# NES_Controller_Board.net
KiCad netlist of a schematic drawn in EAGLE
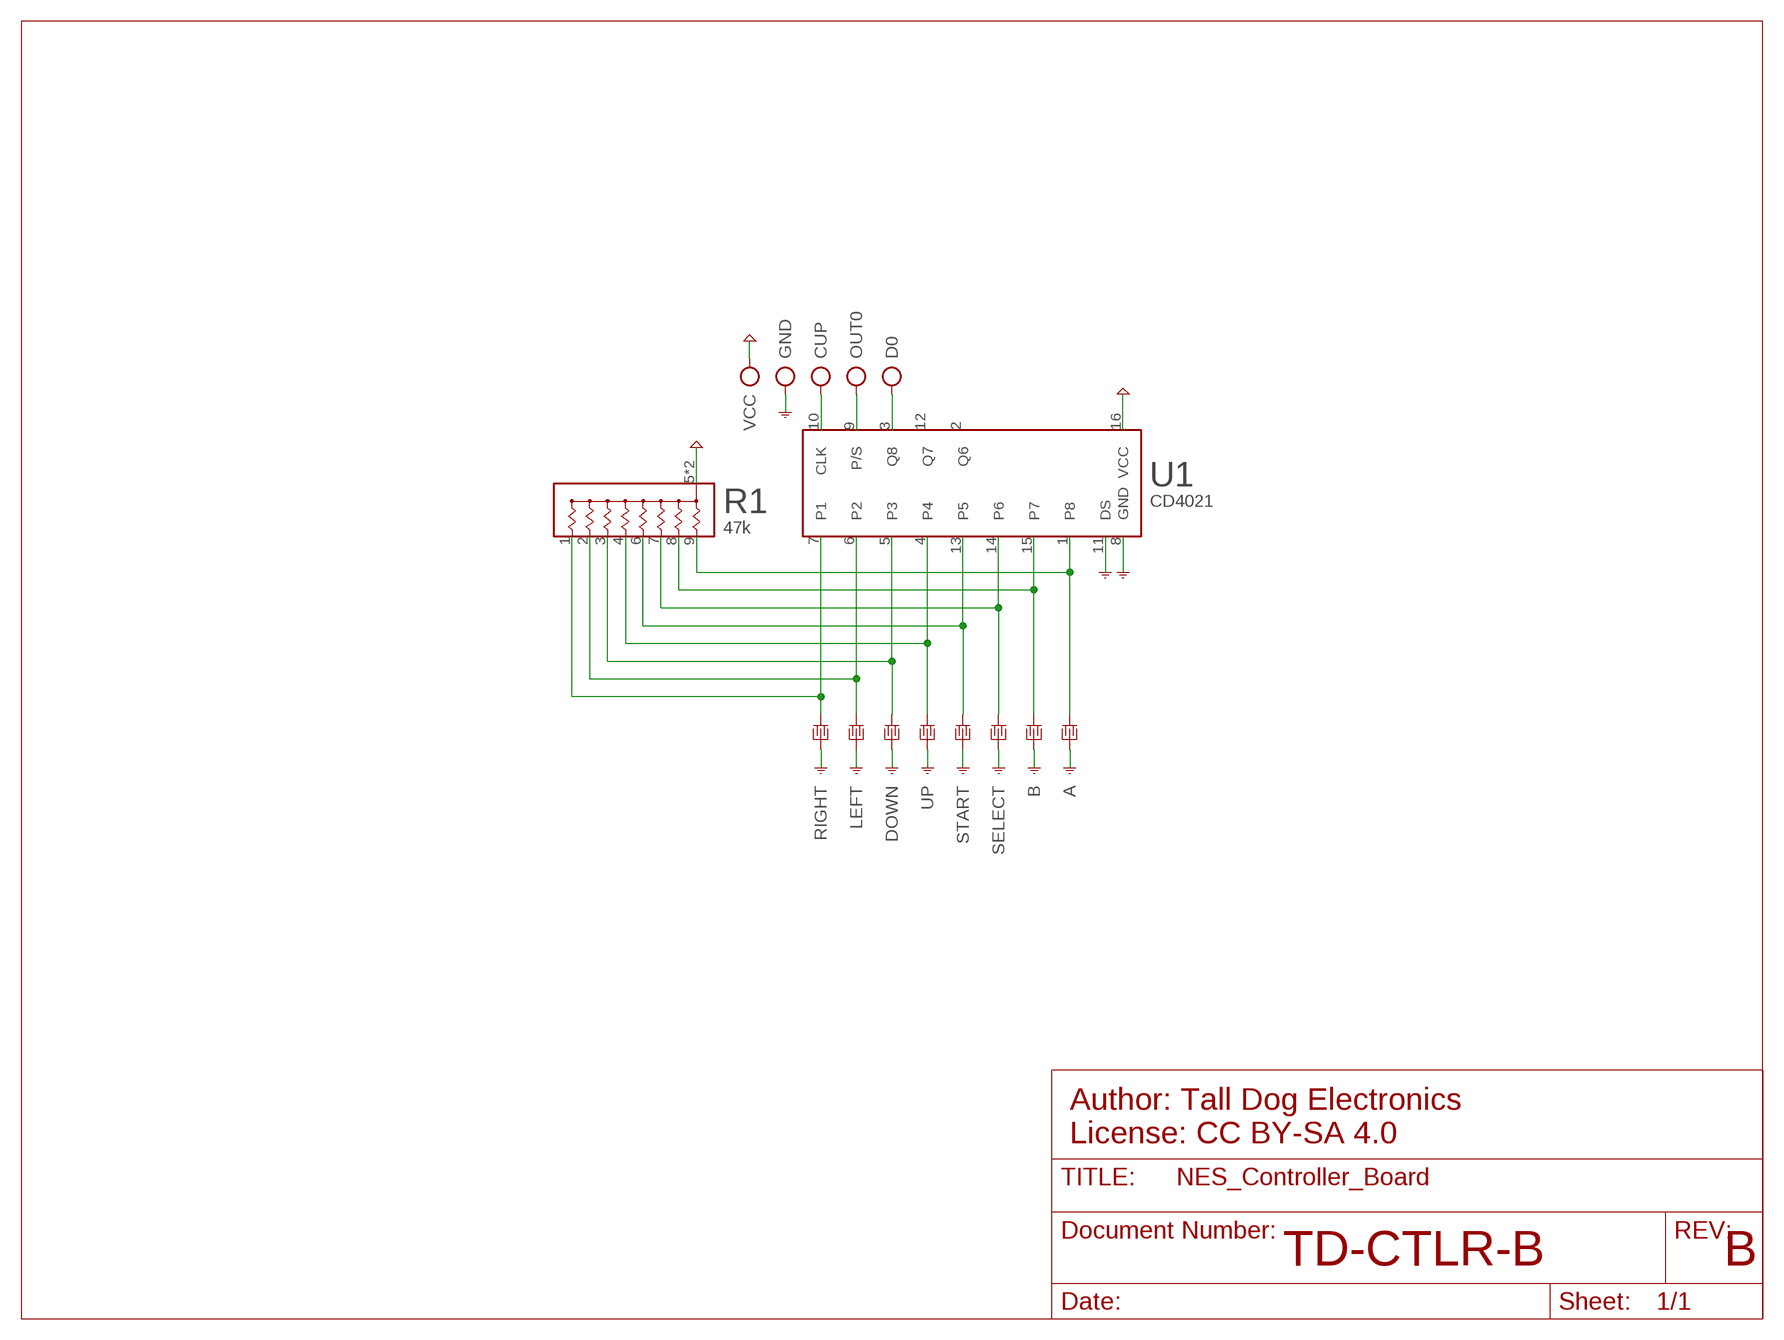
[diagram p0: schematic, sheet 1]

(export (version "E")
  (design (tool "Eeschema 10.0.6"))
  (components
    (comp (ref "A")
      (value "BUTTON-PAD-AB")
      (footprint "eagle-import:CTRL-AB")
      (libsource (lib "eagle-import") (part "BUTTON-PAD-AB"))
    )
    (comp (ref "B")
      (value "BUTTON-PAD-AB")
      (footprint "eagle-import:CTRL-AB")
      (libsource (lib "eagle-import") (part "BUTTON-PAD-AB"))
    )
    (comp (ref "CUP")
      (value "2/RD")
      (footprint "eagle-import:PTH-STRAIN")
      (libsource (lib "eagle-import") (part "HOLE"))
    )
    (comp (ref "D0")
      (value "4/YL")
      (footprint "eagle-import:PTH-STRAIN")
      (libsource (lib "eagle-import") (part "HOLE"))
    )
    (comp (ref "DOWN")
      (value "BUTTON-PAD-DPAD")
      (footprint "eagle-import:CTRL-DPAD")
      (libsource (lib "eagle-import") (part "BUTTON-PAD-DPAD"))
    )
    (comp (ref "GND")
      (value "1/BN")
      (footprint "eagle-import:PTH-STRAIN")
      (libsource (lib "eagle-import") (part "HOLE"))
    )
    (comp (ref "LEFT")
      (value "BUTTON-PAD-DPAD")
      (footprint "eagle-import:CTRL-DPAD")
      (libsource (lib "eagle-import") (part "BUTTON-PAD-DPAD"))
    )
    (comp (ref "OUT0")
      (value "3/OR")
      (footprint "eagle-import:PTH-STRAIN")
      (libsource (lib "eagle-import") (part "HOLE"))
    )
    (comp (ref "R1")
      (value "47k")
      (footprint "eagle-import:EXBA10P")
      (libsource (lib "eagle-import") (part "RA8"))
    )
    (comp (ref "RIGHT")
      (value "BUTTON-PAD-DPAD")
      (footprint "eagle-import:CTRL-DPAD")
      (libsource (lib "eagle-import") (part "BUTTON-PAD-DPAD"))
    )
    (comp (ref "SELECT")
      (value "BUTTON-PAD-STSEL")
      (footprint "eagle-import:CTRL-STSEL")
      (libsource (lib "eagle-import") (part "BUTTON-PAD-STSEL"))
    )
    (comp (ref "START")
      (value "BUTTON-PAD-STSEL")
      (footprint "eagle-import:CTRL-STSEL")
      (libsource (lib "eagle-import") (part "BUTTON-PAD-STSEL"))
    )
    (comp (ref "U1")
      (value "CD4021")
      (footprint "eagle-import:SOIC-16")
      (libsource (lib "eagle-import") (part "CD4021"))
    )
    (comp (ref "UP")
      (value "BUTTON-PAD-DPAD")
      (footprint "eagle-import:CTRL-DPAD")
      (libsource (lib "eagle-import") (part "BUTTON-PAD-DPAD"))
    )
    (comp (ref "VCC")
      (value "5/WH")
      (footprint "eagle-import:PTH-STRAIN")
      (libsource (lib "eagle-import") (part "HOLE"))
    )
  )
  (nets
    (net (code "1") (name "/CUP") (class "Default")
      (node (ref "CUP") (pin "A") (pinfunction "P$1_A") (pintype "bidirectional"))
      (node (ref "CUP") (pin "P") (pinfunction "P$1_P") (pintype "bidirectional"))
      (node (ref "U1") (pin "10") (pinfunction "CLK_10") (pintype "bidirectional"))
    )
    (net (code "2") (name "/D0") (class "Default")
      (node (ref "D0") (pin "A") (pinfunction "P$1_A") (pintype "bidirectional"))
      (node (ref "D0") (pin "P") (pinfunction "P$1_P") (pintype "bidirectional"))
      (node (ref "U1") (pin "3") (pinfunction "Q8_3") (pintype "bidirectional"))
    )
    (net (code "3") (name "/OUT0") (class "Default")
      (node (ref "OUT0") (pin "A") (pinfunction "P$1_A") (pintype "bidirectional"))
      (node (ref "OUT0") (pin "P") (pinfunction "P$1_P") (pintype "bidirectional"))
      (node (ref "U1") (pin "9") (pinfunction "P/S_9") (pintype "bidirectional"))
    )
    (net (code "4") (name "GND") (class "Default")
      (node (ref "A") (pin "A") (pinfunction "A_A") (pintype "bidirectional"))
      (node (ref "B") (pin "A") (pinfunction "A_A") (pintype "bidirectional"))
      (node (ref "DOWN") (pin "A") (pinfunction "A_A") (pintype "bidirectional"))
      (node (ref "GND") (pin "A") (pinfunction "P$1_A") (pintype "bidirectional"))
      (node (ref "GND") (pin "P") (pinfunction "P$1_P") (pintype "bidirectional"))
      (node (ref "LEFT") (pin "A") (pinfunction "A_A") (pintype "bidirectional"))
      (node (ref "RIGHT") (pin "A") (pinfunction "A_A") (pintype "bidirectional"))
      (node (ref "SELECT") (pin "A") (pinfunction "A_A") (pintype "bidirectional"))
      (node (ref "START") (pin "A") (pinfunction "A_A") (pintype "bidirectional"))
      (node (ref "U1") (pin "11") (pinfunction "DS_11") (pintype "bidirectional"))
      (node (ref "U1") (pin "8") (pinfunction "GND_8") (pintype "bidirectional"))
      (node (ref "UP") (pin "A") (pinfunction "A_A") (pintype "bidirectional"))
    )
    (net (code "5") (name "Net-(R1-5)") (class "Default")
      (node (ref "R1") (pin "6") (pinfunction "5_6") (pintype "bidirectional"))
      (node (ref "START") (pin "B") (pinfunction "B_B") (pintype "bidirectional"))
      (node (ref "U1") (pin "13") (pinfunction "P5_13") (pintype "bidirectional"))
    )
    (net (code "6") (name "Net-(R1-6)") (class "Default")
      (node (ref "R1") (pin "7") (pinfunction "6_7") (pintype "bidirectional"))
      (node (ref "SELECT") (pin "B") (pinfunction "B_B") (pintype "bidirectional"))
      (node (ref "U1") (pin "14") (pinfunction "P6_14") (pintype "bidirectional"))
    )
    (net (code "7") (name "Net-(R1-7)") (class "Default")
      (node (ref "B") (pin "B") (pinfunction "B_B") (pintype "bidirectional"))
      (node (ref "R1") (pin "8") (pinfunction "7_8") (pintype "bidirectional"))
      (node (ref "U1") (pin "15") (pinfunction "P7_15") (pintype "bidirectional"))
    )
    (net (code "8") (name "Net-(R1-8)") (class "Default")
      (node (ref "A") (pin "B") (pinfunction "B_B") (pintype "bidirectional"))
      (node (ref "R1") (pin "9") (pinfunction "8_9") (pintype "bidirectional"))
      (node (ref "U1") (pin "1") (pinfunction "P8_1") (pintype "bidirectional"))
    )
    (net (code "9") (name "Net-(U1-P1)") (class "Default")
      (node (ref "R1") (pin "1") (pinfunction "1_1") (pintype "bidirectional"))
      (node (ref "RIGHT") (pin "B") (pinfunction "B_B") (pintype "bidirectional"))
      (node (ref "U1") (pin "7") (pinfunction "P1_7") (pintype "bidirectional"))
    )
    (net (code "10") (name "Net-(U1-P2)") (class "Default")
      (node (ref "LEFT") (pin "B") (pinfunction "B_B") (pintype "bidirectional"))
      (node (ref "R1") (pin "2") (pinfunction "2_2") (pintype "bidirectional"))
      (node (ref "U1") (pin "6") (pinfunction "P2_6") (pintype "bidirectional"))
    )
    (net (code "11") (name "Net-(U1-P3)") (class "Default")
      (node (ref "DOWN") (pin "B") (pinfunction "B_B") (pintype "bidirectional"))
      (node (ref "R1") (pin "3") (pinfunction "3_3") (pintype "bidirectional"))
      (node (ref "U1") (pin "5") (pinfunction "P3_5") (pintype "bidirectional"))
    )
    (net (code "12") (name "Net-(U1-P4)") (class "Default")
      (node (ref "R1") (pin "4") (pinfunction "4_4") (pintype "bidirectional"))
      (node (ref "U1") (pin "4") (pinfunction "P4_4") (pintype "bidirectional"))
      (node (ref "UP") (pin "B") (pinfunction "B_B") (pintype "bidirectional"))
    )
    (net (code "13") (name "VCC") (class "Default")
      (node (ref "R1") (pin "10") (pinfunction "COM_10") (pintype "bidirectional"))
      (node (ref "R1") (pin "5") (pinfunction "COM_5") (pintype "bidirectional"))
      (node (ref "U1") (pin "16") (pinfunction "VCC_16") (pintype "bidirectional"))
      (node (ref "VCC") (pin "A") (pinfunction "P$1_A") (pintype "bidirectional"))
      (node (ref "VCC") (pin "P") (pinfunction "P$1_P") (pintype "bidirectional"))
    )
    (net (code "14") (name "unconnected-(U1-Q6-Pad2)") (class "Default")
      (node (ref "U1") (pin "2") (pinfunction "Q6_2") (pintype "bidirectional"))
    )
    (net (code "15") (name "unconnected-(U1-Q7-Pad12)") (class "Default")
      (node (ref "U1") (pin "12") (pinfunction "Q7_12") (pintype "bidirectional"))
    )
  )
)
